# Sch.net
KiCad netlist of a schematic drawn in Altium Designer
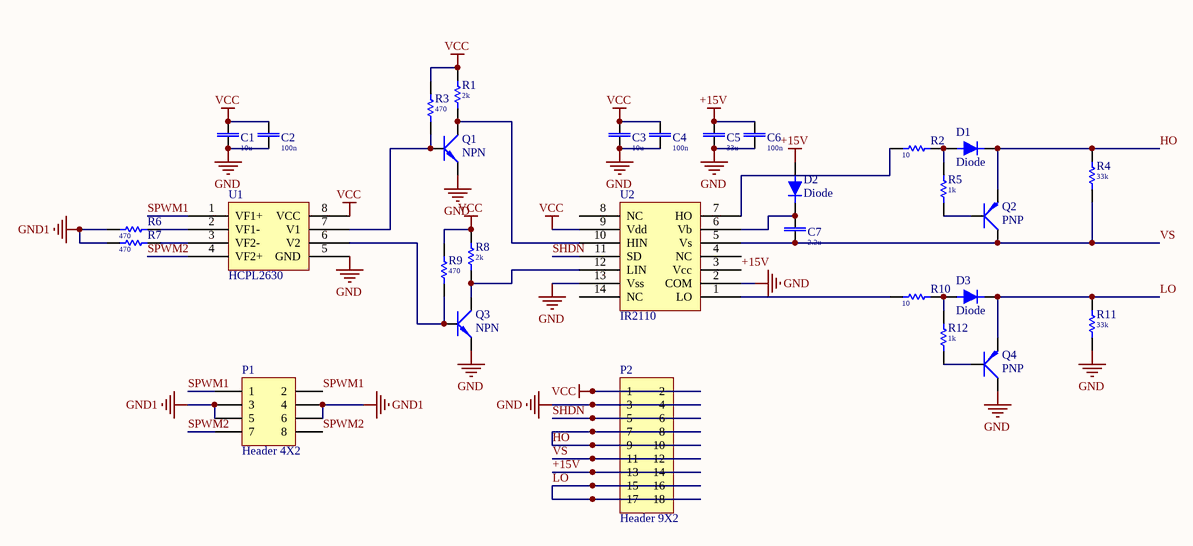
[diagram p0: Sch.SchDoc]

(export (version "E")
  (design (tool "Eeschema 10.0.6"))
  (components
    (comp (ref "C1")
      (value "10u")
      (footprint "CAP0805")
      (description "Capacitor")
      (fields (field (name "Comment") "Cap") (field (name "PUBLISHER") "Altium Limited"))
      (libsource (lib "Miscellaneous Devices") (part "Cap"))
    )
    (comp (ref "C2")
      (value "100n")
      (footprint "CAP0603")
      (description "Capacitor")
      (fields (field (name "Comment") "Cap") (field (name "PUBLISHER") "Altium Limited"))
      (libsource (lib "Miscellaneous Devices") (part "Cap"))
    )
    (comp (ref "C3")
      (value "10u")
      (footprint "CAP0805")
      (description "Capacitor")
      (fields (field (name "Comment") "Cap") (field (name "PUBLISHER") "Altium Limited"))
      (libsource (lib "Miscellaneous Devices") (part "Cap"))
    )
    (comp (ref "C4")
      (value "100n")
      (footprint "CAP0603")
      (description "Capacitor")
      (fields (field (name "Comment") "Cap") (field (name "PUBLISHER") "Altium Limited"))
      (libsource (lib "Miscellaneous Devices") (part "Cap"))
    )
    (comp (ref "C5")
      (value "33u")
      (footprint "CAP 2.5*5*11")
      (description "Capacitor")
      (fields (field (name "Comment") "Cap") (field (name "PUBLISHER") "Altium Limited"))
      (libsource (lib "Miscellaneous Devices") (part "Cap"))
    )
    (comp (ref "C6")
      (value "100n")
      (footprint "CAP0603")
      (description "Capacitor")
      (fields (field (name "Comment") "Cap") (field (name "PUBLISHER") "Altium Limited"))
      (libsource (lib "Miscellaneous Devices") (part "Cap"))
    )
    (comp (ref "C7")
      (value "2.2u")
      (footprint "CAP0805")
      (description "Capacitor")
      (fields (field (name "Comment") "Cap") (field (name "PUBLISHER") "Altium Limited"))
      (libsource (lib "Miscellaneous Devices") (part "Cap"))
    )
    (comp (ref "D1")
      (value "Diode")
      (footprint "DIODE_SMA")
      (description "Default Diode")
      (fields (field (name "PUBLISHER") "Altium Limited"))
      (libsource (lib "Miscellaneous Devices") (part "Diode"))
    )
    (comp (ref "D2")
      (value "Diode")
      (footprint "DIODE_SMA")
      (description "Default Diode")
      (fields (field (name "PUBLISHER") "Altium Limited"))
      (libsource (lib "Miscellaneous Devices") (part "Diode"))
    )
    (comp (ref "D3")
      (value "Diode")
      (footprint "DIODE_SMA")
      (description "Default Diode")
      (fields (field (name "PUBLISHER") "Altium Limited"))
      (libsource (lib "Miscellaneous Devices") (part "Diode"))
    )
    (comp (ref "P1")
      (value "Header 4X2")
      (footprint "HDR2X4")
      (description "Header, 4-Pin, Dual row")
      (fields (field (name "PUBLISHER") "Altium Limited"))
      (libsource (lib "Miscellaneous Connectors") (part "Header 4X2"))
    )
    (comp (ref "P2")
      (value "Header 9X2")
      (footprint "HDR2X9")
      (description "Header, 9-Pin, Dual row")
      (fields (field (name "PUBLISHER") "Altium Limited"))
      (libsource (lib "Miscellaneous Connectors") (part "Header 9X2"))
    )
    (comp (ref "Q1")
      (value "NPN")
      (footprint "BJT")
      (description "NPN Bipolar Transistor")
      (fields (field (name "PUBLISHER") "Altium Limited"))
      (libsource (lib "Miscellaneous Devices") (part "NPN"))
    )
    (comp (ref "Q2")
      (value "PNP")
      (footprint "BJT")
      (description "PNP Bipolar Transistor")
      (fields (field (name "PUBLISHER") "Altium Limited"))
      (libsource (lib "Miscellaneous Devices") (part "PNP"))
    )
    (comp (ref "Q3")
      (value "NPN")
      (footprint "BJT")
      (description "NPN Bipolar Transistor")
      (fields (field (name "PUBLISHER") "Altium Limited"))
      (libsource (lib "Miscellaneous Devices") (part "NPN"))
    )
    (comp (ref "Q4")
      (value "PNP")
      (footprint "BJT")
      (description "PNP Bipolar Transistor")
      (fields (field (name "PUBLISHER") "Altium Limited"))
      (libsource (lib "Miscellaneous Devices") (part "PNP"))
    )
    (comp (ref "R1")
      (value "2k")
      (footprint "RES0603")
      (description "Resistor")
      (fields (field (name "PUBLISHER") "Altium Limited"))
      (libsource (lib "Miscellaneous Devices") (part "Res1"))
    )
    (comp (ref "R2")
      (value "10")
      (footprint "RES0603")
      (description "Resistor")
      (fields (field (name "PUBLISHER") "Altium Limited"))
      (libsource (lib "Miscellaneous Devices") (part "Res1"))
    )
    (comp (ref "R3")
      (value "470")
      (footprint "RES0603")
      (description "Resistor")
      (fields (field (name "PUBLISHER") "Altium Limited"))
      (libsource (lib "Miscellaneous Devices") (part "Res1"))
    )
    (comp (ref "R4")
      (value "33k")
      (footprint "RES0603")
      (description "Resistor")
      (fields (field (name "PUBLISHER") "Altium Limited"))
      (libsource (lib "Miscellaneous Devices") (part "Res1"))
    )
    (comp (ref "R5")
      (value "1k")
      (footprint "RES0603")
      (description "Resistor")
      (fields (field (name "PUBLISHER") "Altium Limited"))
      (libsource (lib "Miscellaneous Devices") (part "Res1"))
    )
    (comp (ref "R6")
      (value "470")
      (footprint "RES0603")
      (description "Resistor")
      (fields (field (name "PUBLISHER") "Altium Limited"))
      (libsource (lib "Miscellaneous Devices") (part "Res1"))
    )
    (comp (ref "R7")
      (value "470")
      (footprint "RES0603")
      (description "Resistor")
      (fields (field (name "PUBLISHER") "Altium Limited"))
      (libsource (lib "Miscellaneous Devices") (part "Res1"))
    )
    (comp (ref "R8")
      (value "2k")
      (footprint "RES0603")
      (description "Resistor")
      (fields (field (name "PUBLISHER") "Altium Limited"))
      (libsource (lib "Miscellaneous Devices") (part "Res1"))
    )
    (comp (ref "R9")
      (value "470")
      (footprint "RES0603")
      (description "Resistor")
      (fields (field (name "PUBLISHER") "Altium Limited"))
      (libsource (lib "Miscellaneous Devices") (part "Res1"))
    )
    (comp (ref "R10")
      (value "10")
      (footprint "RES0603")
      (description "Resistor")
      (fields (field (name "PUBLISHER") "Altium Limited"))
      (libsource (lib "Miscellaneous Devices") (part "Res1"))
    )
    (comp (ref "R11")
      (value "33k")
      (footprint "RES0603")
      (description "Resistor")
      (fields (field (name "PUBLISHER") "Altium Limited"))
      (libsource (lib "Miscellaneous Devices") (part "Res1"))
    )
    (comp (ref "R12")
      (value "1k")
      (footprint "RES0603")
      (description "Resistor")
      (fields (field (name "PUBLISHER") "Altium Limited"))
      (libsource (lib "Miscellaneous Devices") (part "Res1"))
    )
    (comp (ref "U1") (value "HCPL2630") (footprint "DIP-8") (libsource (lib "MySchlib") (part "HCPL2630")))
    (comp (ref "U2") (value "IR2110") (footprint "DIP-14") (libsource (lib "MySchlib") (part "IR2110")))
  )
  (nets
    (net (code "1") (name "+15V") (class "Default")
      (node (ref "C5") (pin "1") (pinfunction "1_1") (pintype "passive"))
      (node (ref "C6") (pin "1") (pinfunction "1_1") (pintype "passive"))
      (node (ref "D2") (pin "1") (pinfunction "A_1") (pintype "passive"))
      (node (ref "P2") (pin "13") (pinfunction "13_13") (pintype "passive"))
      (node (ref "P2") (pin "14") (pinfunction "14_14") (pintype "passive"))
      (node (ref "U2") (pin "3") (pinfunction "Vcc_3") (pintype "passive"))
    )
    (net (code "2") (name "/HO") (class "Default")
      (node (ref "D1") (pin "2") (pinfunction "K_2") (pintype "passive"))
      (node (ref "P2") (pin "10") (pinfunction "10_10") (pintype "passive"))
      (node (ref "P2") (pin "7") (pinfunction "7_7") (pintype "passive"))
      (node (ref "P2") (pin "8") (pinfunction "8_8") (pintype "passive"))
      (node (ref "P2") (pin "9") (pinfunction "9_9") (pintype "passive"))
      (node (ref "Q2") (pin "3") (pinfunction "E_3") (pintype "passive"))
      (node (ref "R4") (pin "1") (pinfunction "1_1") (pintype "passive"))
    )
    (net (code "3") (name "/LO") (class "Default")
      (node (ref "D3") (pin "2") (pinfunction "K_2") (pintype "passive"))
      (node (ref "P2") (pin "15") (pinfunction "15_15") (pintype "passive"))
      (node (ref "P2") (pin "16") (pinfunction "16_16") (pintype "passive"))
      (node (ref "P2") (pin "17") (pinfunction "17_17") (pintype "passive"))
      (node (ref "P2") (pin "18") (pinfunction "18_18") (pintype "passive"))
      (node (ref "Q4") (pin "3") (pinfunction "E_3") (pintype "passive"))
      (node (ref "R11") (pin "1") (pinfunction "1_1") (pintype "passive"))
    )
    (net (code "4") (name "/SHDN") (class "Default")
      (node (ref "P2") (pin "5") (pinfunction "5_5") (pintype "passive"))
      (node (ref "P2") (pin "6") (pinfunction "6_6") (pintype "passive"))
      (node (ref "U2") (pin "11") (pinfunction "SD_11") (pintype "passive"))
    )
    (net (code "5") (name "/SPWM1") (class "Default")
      (node (ref "P1") (pin "1") (pinfunction "1_1") (pintype "passive"))
      (node (ref "P1") (pin "2") (pinfunction "2_2") (pintype "passive"))
      (node (ref "U1") (pin "1") (pinfunction "VF1+_1") (pintype "passive"))
    )
    (net (code "6") (name "/SPWM2") (class "Default")
      (node (ref "P1") (pin "7") (pinfunction "7_7") (pintype "passive"))
      (node (ref "P1") (pin "8") (pinfunction "8_8") (pintype "passive"))
      (node (ref "U1") (pin "4") (pinfunction "VF2+_4") (pintype "passive"))
    )
    (net (code "7") (name "/VS") (class "Default")
      (node (ref "C7") (pin "2") (pinfunction "2_2") (pintype "passive"))
      (node (ref "P2") (pin "11") (pinfunction "11_11") (pintype "passive"))
      (node (ref "P2") (pin "12") (pinfunction "12_12") (pintype "passive"))
      (node (ref "Q2") (pin "1") (pinfunction "C_1") (pintype "passive"))
      (node (ref "R4") (pin "2") (pinfunction "2_2") (pintype "passive"))
      (node (ref "U2") (pin "5") (pinfunction "Vs_5") (pintype "passive"))
    )
    (net (code "8") (name "GND") (class "Default")
      (node (ref "C1") (pin "2") (pinfunction "2_2") (pintype "passive"))
      (node (ref "C2") (pin "2") (pinfunction "2_2") (pintype "passive"))
      (node (ref "C3") (pin "2") (pinfunction "2_2") (pintype "passive"))
      (node (ref "C4") (pin "2") (pinfunction "2_2") (pintype "passive"))
      (node (ref "C5") (pin "2") (pinfunction "2_2") (pintype "passive"))
      (node (ref "C6") (pin "2") (pinfunction "2_2") (pintype "passive"))
      (node (ref "P2") (pin "3") (pinfunction "3_3") (pintype "passive"))
      (node (ref "P2") (pin "4") (pinfunction "4_4") (pintype "passive"))
      (node (ref "Q1") (pin "3") (pinfunction "E_3") (pintype "passive"))
      (node (ref "Q3") (pin "3") (pinfunction "E_3") (pintype "passive"))
      (node (ref "Q4") (pin "1") (pinfunction "C_1") (pintype "passive"))
      (node (ref "R11") (pin "2") (pinfunction "2_2") (pintype "passive"))
      (node (ref "U1") (pin "5") (pinfunction "GND_5") (pintype "passive"))
      (node (ref "U2") (pin "13") (pinfunction "Vss_13") (pintype "passive"))
      (node (ref "U2") (pin "2") (pinfunction "COM_2") (pintype "passive"))
    )
    (net (code "9") (name "GND1") (class "Default")
      (node (ref "P1") (pin "3") (pinfunction "3_3") (pintype "passive"))
      (node (ref "P1") (pin "4") (pinfunction "4_4") (pintype "passive"))
      (node (ref "P1") (pin "5") (pinfunction "5_5") (pintype "passive"))
      (node (ref "P1") (pin "6") (pinfunction "6_6") (pintype "passive"))
      (node (ref "R6") (pin "1") (pinfunction "1_1") (pintype "passive"))
      (node (ref "R7") (pin "1") (pinfunction "1_1") (pintype "passive"))
    )
    (net (code "10") (name "Net-(D1-A)") (class "Default")
      (node (ref "D1") (pin "1") (pinfunction "A_1") (pintype "passive"))
      (node (ref "R2") (pin "1") (pinfunction "1_1") (pintype "passive"))
      (node (ref "R5") (pin "1") (pinfunction "1_1") (pintype "passive"))
    )
    (net (code "11") (name "Net-(D2-K)") (class "Default")
      (node (ref "C7") (pin "1") (pinfunction "1_1") (pintype "passive"))
      (node (ref "D2") (pin "2") (pinfunction "K_2") (pintype "passive"))
      (node (ref "U2") (pin "6") (pinfunction "Vb_6") (pintype "passive"))
    )
    (net (code "12") (name "Net-(D3-A)") (class "Default")
      (node (ref "D3") (pin "1") (pinfunction "A_1") (pintype "passive"))
      (node (ref "R10") (pin "1") (pinfunction "1_1") (pintype "passive"))
      (node (ref "R12") (pin "1") (pinfunction "1_1") (pintype "passive"))
    )
    (net (code "13") (name "Net-(Q1-B)") (class "Default")
      (node (ref "Q1") (pin "2") (pinfunction "B_2") (pintype "passive"))
      (node (ref "R3") (pin "2") (pinfunction "2_2") (pintype "passive"))
      (node (ref "U1") (pin "7") (pinfunction "V1_7") (pintype "passive"))
    )
    (net (code "14") (name "Net-(Q1-C)") (class "Default")
      (node (ref "Q1") (pin "1") (pinfunction "C_1") (pintype "passive"))
      (node (ref "R1") (pin "1") (pinfunction "1_1") (pintype "passive"))
      (node (ref "U2") (pin "10") (pinfunction "HIN_10") (pintype "passive"))
    )
    (net (code "15") (name "Net-(Q2-B)") (class "Default")
      (node (ref "Q2") (pin "2") (pinfunction "B_2") (pintype "passive"))
      (node (ref "R5") (pin "2") (pinfunction "2_2") (pintype "passive"))
    )
    (net (code "16") (name "Net-(Q3-B)") (class "Default")
      (node (ref "Q3") (pin "2") (pinfunction "B_2") (pintype "passive"))
      (node (ref "R9") (pin "2") (pinfunction "2_2") (pintype "passive"))
      (node (ref "U1") (pin "6") (pinfunction "V2_6") (pintype "passive"))
    )
    (net (code "17") (name "Net-(Q3-C)") (class "Default")
      (node (ref "Q3") (pin "1") (pinfunction "C_1") (pintype "passive"))
      (node (ref "R8") (pin "1") (pinfunction "1_1") (pintype "passive"))
      (node (ref "U2") (pin "12") (pinfunction "LIN_12") (pintype "passive"))
    )
    (net (code "18") (name "Net-(Q4-B)") (class "Default")
      (node (ref "Q4") (pin "2") (pinfunction "B_2") (pintype "passive"))
      (node (ref "R12") (pin "2") (pinfunction "2_2") (pintype "passive"))
    )
    (net (code "19") (name "Net-(U1-VF1-)") (class "Default")
      (node (ref "R6") (pin "2") (pinfunction "2_2") (pintype "passive"))
      (node (ref "U1") (pin "2") (pinfunction "VF1-_2") (pintype "passive"))
    )
    (net (code "20") (name "Net-(U1-VF2-)") (class "Default")
      (node (ref "R7") (pin "2") (pinfunction "2_2") (pintype "passive"))
      (node (ref "U1") (pin "3") (pinfunction "VF2-_3") (pintype "passive"))
    )
    (net (code "21") (name "Net-(U2-HO)") (class "Default")
      (node (ref "R2") (pin "2") (pinfunction "2_2") (pintype "passive"))
      (node (ref "U2") (pin "7") (pinfunction "HO_7") (pintype "passive"))
    )
    (net (code "22") (name "Net-(U2-LO)") (class "Default")
      (node (ref "R10") (pin "2") (pinfunction "2_2") (pintype "passive"))
      (node (ref "U2") (pin "1") (pinfunction "LO_1") (pintype "passive"))
    )
    (net (code "23") (name "VCC") (class "Default")
      (node (ref "C1") (pin "1") (pinfunction "1_1") (pintype "passive"))
      (node (ref "C2") (pin "1") (pinfunction "1_1") (pintype "passive"))
      (node (ref "C3") (pin "1") (pinfunction "1_1") (pintype "passive"))
      (node (ref "C4") (pin "1") (pinfunction "1_1") (pintype "passive"))
      (node (ref "P2") (pin "1") (pinfunction "1_1") (pintype "passive"))
      (node (ref "P2") (pin "2") (pinfunction "2_2") (pintype "passive"))
      (node (ref "R1") (pin "2") (pinfunction "2_2") (pintype "passive"))
      (node (ref "R3") (pin "1") (pinfunction "1_1") (pintype "passive"))
      (node (ref "R8") (pin "2") (pinfunction "2_2") (pintype "passive"))
      (node (ref "R9") (pin "1") (pinfunction "1_1") (pintype "passive"))
      (node (ref "U1") (pin "8") (pinfunction "VCC_8") (pintype "passive"))
      (node (ref "U2") (pin "9") (pinfunction "Vdd_9") (pintype "passive"))
    )
    (net (code "24") (name "unconnected-(U2-NC-Pad4)") (class "Default")
      (node (ref "U2") (pin "4") (pinfunction "NC_4") (pintype "passive"))
    )
    (net (code "25") (name "unconnected-(U2-NC-Pad8)") (class "Default")
      (node (ref "U2") (pin "8") (pinfunction "NC_8") (pintype "passive"))
    )
    (net (code "26") (name "unconnected-(U2-NC-Pad14)") (class "Default")
      (node (ref "U2") (pin "14") (pinfunction "NC_14") (pintype "passive"))
    )
  )
)
